# KNX-MultiExt_2.net
KiCad netlist of a schematic drawn in Altium Designer
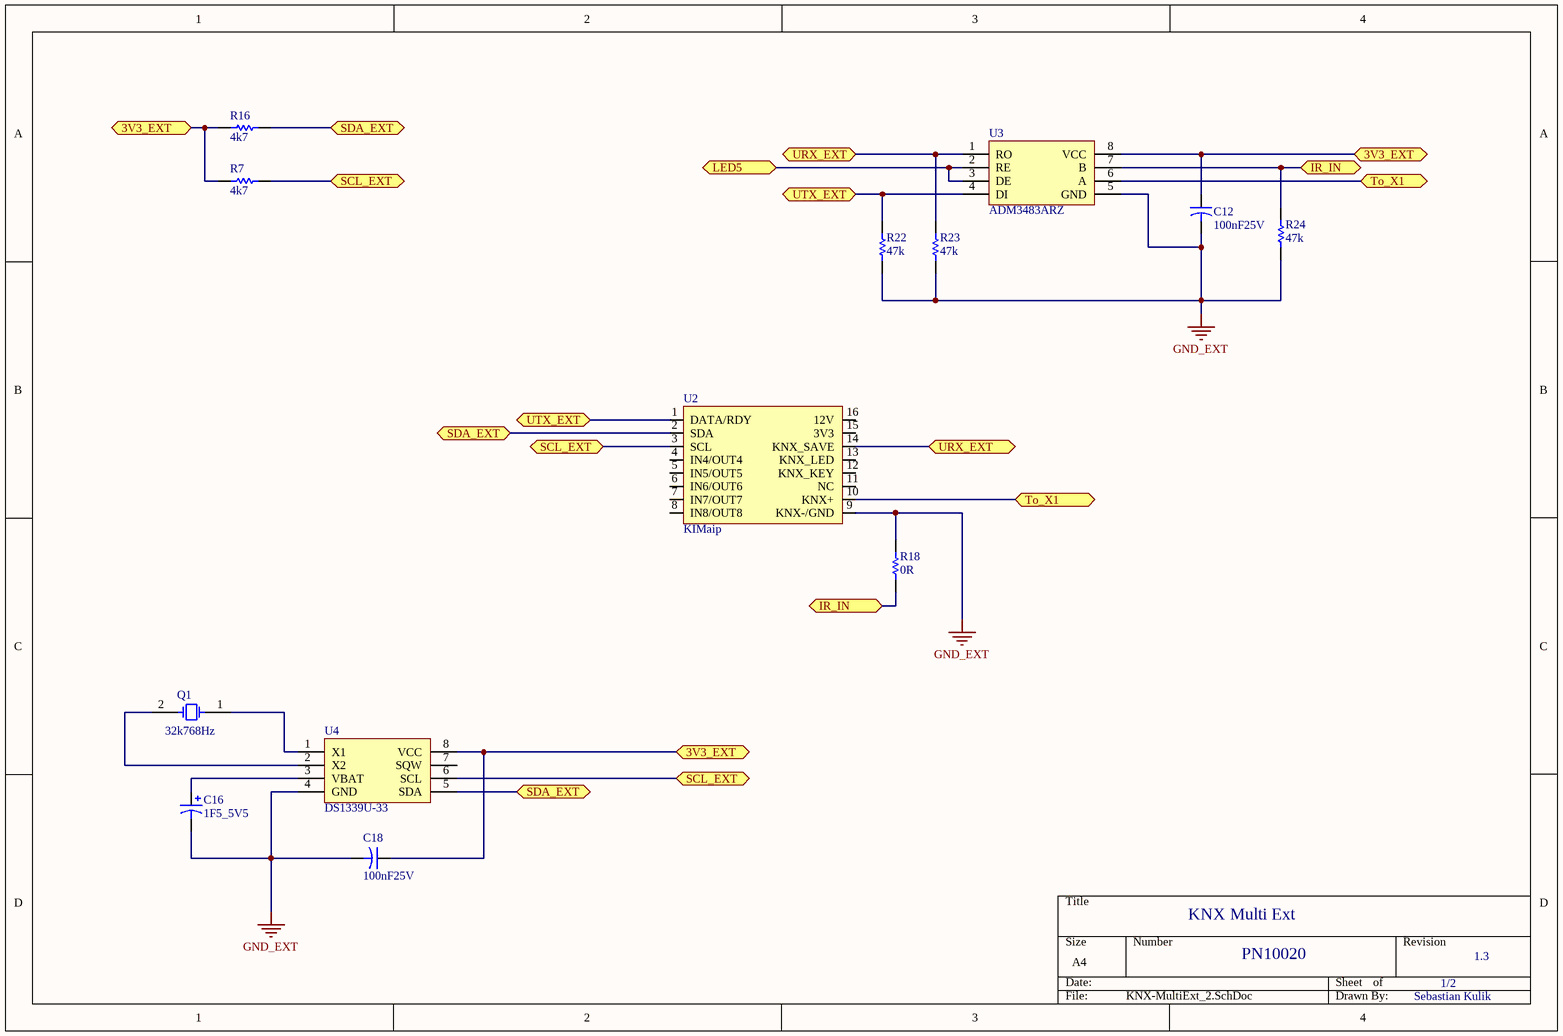
[diagram p0: KNX-MultiExt_2.SchDoc]

(export (version "E")
  (design (tool "Eeschema 10.0.6"))
  (components
    (comp (ref "C12")
      (value "100nF25V")
      (footprint "C0402")
      (description "AVX, X5R, 10%, 25V")
      (fields
        (field (name "MANUFACTURER") "AVX")
        (field (name "Comment") "100nF25V_0402")
        (field (name "PUBLISHER") "Sebastian Kulik")
      )
      (libsource (lib "Capacitors") (part "100nF25V_0402"))
    )
    (comp (ref "C16")
      (value "1F5_5V5")
      (footprint "Goldcap_B")
      (description "Panasonic, F series")
      (fields
        (field (name "MANUFACTURER") "Panasonic")
        (field (name "Comment") "1F5_5V5_POL")
        (field (name "PUBLISHER") "Sebastian Kulik")
      )
      (libsource (lib "Capacitors") (part "1F5_5V5_POL"))
    )
    (comp (ref "C18")
      (value "100nF25V")
      (footprint "C0402")
      (description "AVX, X5R, 10%, 25V")
      (fields
        (field (name "MANUFACTURER") "AVX")
        (field (name "Comment") "100nF25V_0402")
        (field (name "PUBLISHER") "Sebastian Kulik")
      )
      (libsource (lib "Capacitors") (part "100nF25V_0402"))
    )
    (comp (ref "Q1")
      (value "32k768Hz")
      (footprint "VT-200")
      (description "Crystal, 32.768kHz")
      (fields
        (field (name "MANUFACTURER") "Seiko")
        (field (name "Comment") "Crystal_32k768Hz")
        (field (name "PUBLISHER") "Sebastian Kulik")
      )
      (libsource (lib "Passives") (part "Crystal_32k768Hz"))
    )
    (comp (ref "R7")
      (value "4k7")
      (footprint "R0402")
      (description "Vishay CRCW series, 63mW, 1%")
      (fields
        (field (name "MANUFACTURER") "Vishay")
        (field (name "Comment") "4k7_0402")
        (field (name "PUBLISHER") "Sebastian Kulik")
      )
      (libsource (lib "Resistors") (part "4k7_0402"))
    )
    (comp (ref "R16")
      (value "4k7")
      (footprint "R0402")
      (description "Vishay CRCW series, 63mW, 1%")
      (fields
        (field (name "MANUFACTURER") "Vishay")
        (field (name "Comment") "4k7_0402")
        (field (name "PUBLISHER") "Sebastian Kulik")
      )
      (libsource (lib "Resistors") (part "4k7_0402"))
    )
    (comp (ref "R18")
      (value "0R")
      (footprint "R0603(1608)")
      (description "Vishay, CRCW series, 100mW")
      (fields
        (field (name "MANUFACTURER") "Vishay")
        (field (name "Comment") "0R_0603")
        (field (name "PUBLISHER") "Sebastian Kulik")
      )
      (libsource (lib "Resistors") (part "0R_0603"))
    )
    (comp (ref "R22")
      (value "47k")
      (footprint "R0402")
      (description "Vishay CRCW series, 63mW, 1%")
      (fields
        (field (name "MANUFACTURER") "Vishay")
        (field (name "Comment") "47k_0402")
        (field (name "PUBLISHER") "Sebastian Kulik")
      )
      (libsource (lib "Resistors") (part "47k_0402"))
    )
    (comp (ref "R23")
      (value "47k")
      (footprint "R0402")
      (description "Vishay CRCW series, 63mW, 1%")
      (fields
        (field (name "MANUFACTURER") "Vishay")
        (field (name "Comment") "47k_0402")
        (field (name "PUBLISHER") "Sebastian Kulik")
      )
      (libsource (lib "Resistors") (part "47k_0402"))
    )
    (comp (ref "R24")
      (value "47k")
      (footprint "R0402")
      (description "Vishay CRCW series, 63mW, 1%")
      (fields
        (field (name "MANUFACTURER") "Vishay")
        (field (name "Comment") "47k_0402")
        (field (name "PUBLISHER") "Sebastian Kulik")
      )
      (libsource (lib "Resistors") (part "47k_0402"))
    )
    (comp (ref "U2")
      (value "KIMaip")
      (footprint "KIMaip")
      (description "PoE, 12V")
      (fields (field (name "MANUFACTURER") "Tapko") (field (name "PUBLISHER") "Sebastian Kulik"))
      (libsource (lib "ICs") (part "KIMaip"))
    )
    (comp (ref "U3")
      (value "ADM3483ARZ")
      (footprint "SOIC8_N")
      (description "Transceiver, RS485/422")
      (fields (field (name "MANUFACTURER") "ADI") (field (name "PUBLISHER") "Sebastian Kulik"))
      (libsource (lib "ICs") (part "ADM3483ARZ"))
    )
    (comp (ref "U4")
      (value "DS1339U-33")
      (footprint "uSOP8")
      (description "RTC")
      (fields (field (name "MANUFACTURER") "Dallas") (field (name "PUBLISHER") "Sebastian Kulik"))
      (libsource (lib "ICs") (part "DS1339U-33"))
    )
  )
  (nets
    (net (code "1") (name "/3V3_EXT") (class "Default")
      (node (ref "C12") (pin "1") (pinfunction "1_1") (pintype "passive"))
      (node (ref "C18") (pin "1") (pinfunction "1_1") (pintype "passive"))
      (node (ref "R16") (pin "1") (pinfunction "1_1") (pintype "passive"))
      (node (ref "R7") (pin "1") (pinfunction "1_1") (pintype "passive"))
      (node (ref "U3") (pin "8") (pinfunction "VCC_8") (pintype "power_in"))
      (node (ref "U4") (pin "8") (pinfunction "VCC_8") (pintype "power_in"))
    )
    (net (code "2") (name "/IR_IN") (class "Default")
      (node (ref "R18") (pin "1") (pinfunction "1_1") (pintype "passive"))
      (node (ref "R24") (pin "2") (pinfunction "2_2") (pintype "passive"))
      (node (ref "U3") (pin "7") (pinfunction "B_7") (pintype "passive"))
    )
    (net (code "3") (name "/LED5") (class "Default")
      (node (ref "U3") (pin "2") (pinfunction "RE_2") (pintype "passive"))
      (node (ref "U3") (pin "3") (pinfunction "DE_3") (pintype "passive"))
    )
    (net (code "4") (name "/SCL_EXT") (class "Default")
      (node (ref "R7") (pin "2") (pinfunction "2_2") (pintype "passive"))
      (node (ref "U2") (pin "3") (pinfunction "SCL_3") (pintype "passive"))
      (node (ref "U4") (pin "6") (pinfunction "SCL_6") (pintype "passive"))
    )
    (net (code "5") (name "/SDA_EXT") (class "Default")
      (node (ref "R16") (pin "2") (pinfunction "2_2") (pintype "passive"))
      (node (ref "U2") (pin "2") (pinfunction "SDA_2") (pintype "passive"))
      (node (ref "U4") (pin "5") (pinfunction "SDA_5") (pintype "passive"))
    )
    (net (code "6") (name "/To_X1") (class "Default")
      (node (ref "U2") (pin "10") (pinfunction "KNX+_10") (pintype "passive"))
      (node (ref "U3") (pin "6") (pinfunction "A_6") (pintype "passive"))
    )
    (net (code "7") (name "/URX_EXT") (class "Default")
      (node (ref "R23") (pin "2") (pinfunction "2_2") (pintype "passive"))
      (node (ref "U2") (pin "14") (pinfunction "KNX_SAVE_14") (pintype "passive"))
      (node (ref "U3") (pin "1") (pinfunction "RO_1") (pintype "passive"))
    )
    (net (code "8") (name "/UTX_EXT") (class "Default")
      (node (ref "R22") (pin "2") (pinfunction "2_2") (pintype "passive"))
      (node (ref "U2") (pin "1") (pinfunction "DATA/RDY_1") (pintype "passive"))
      (node (ref "U3") (pin "4") (pinfunction "DI_4") (pintype "passive"))
    )
    (net (code "9") (name "GND_EXT") (class "Default")
      (node (ref "C12") (pin "2") (pinfunction "2_2") (pintype "passive"))
      (node (ref "C16") (pin "2") (pinfunction "2_2") (pintype "passive"))
      (node (ref "C18") (pin "2") (pinfunction "2_2") (pintype "passive"))
      (node (ref "R18") (pin "2") (pinfunction "2_2") (pintype "passive"))
      (node (ref "R22") (pin "1") (pinfunction "1_1") (pintype "passive"))
      (node (ref "R23") (pin "1") (pinfunction "1_1") (pintype "passive"))
      (node (ref "R24") (pin "1") (pinfunction "1_1") (pintype "passive"))
      (node (ref "U2") (pin "9") (pinfunction "KNX-/GND_9") (pintype "passive"))
      (node (ref "U3") (pin "5") (pinfunction "GND_5") (pintype "passive"))
      (node (ref "U4") (pin "4") (pinfunction "GND_4") (pintype "passive"))
    )
    (net (code "10") (name "Net-(Q1-E{slash}D)") (class "Default")
      (node (ref "Q1") (pin "1") (pinfunction "E/D_1") (pintype "passive"))
      (node (ref "U4") (pin "1") (pinfunction "X1_1") (pintype "passive"))
    )
    (net (code "11") (name "Net-(Q1-GND)") (class "Default")
      (node (ref "Q1") (pin "2") (pinfunction "GND_2") (pintype "passive"))
      (node (ref "U4") (pin "2") (pinfunction "X2_2") (pintype "passive"))
    )
    (net (code "12") (name "Net-(U4-VBAT)") (class "Default")
      (node (ref "C16") (pin "1") (pinfunction "1_1") (pintype "passive"))
      (node (ref "U4") (pin "3") (pinfunction "VBAT_3") (pintype "passive"))
    )
    (net (code "13") (name "unconnected-(U2-3V3-Pad15)") (class "Default")
      (node (ref "U2") (pin "15") (pinfunction "3V3_15") (pintype "passive"))
    )
    (net (code "14") (name "unconnected-(U2-12V-Pad16)") (class "Default")
      (node (ref "U2") (pin "16") (pinfunction "12V_16") (pintype "passive"))
    )
    (net (code "15") (name "unconnected-(U2-IN4{slash}OUT4-Pad4)") (class "Default")
      (node (ref "U2") (pin "4") (pinfunction "IN4/OUT4_4") (pintype "passive"))
    )
    (net (code "16") (name "unconnected-(U2-IN5{slash}OUT5-Pad5)") (class "Default")
      (node (ref "U2") (pin "5") (pinfunction "IN5/OUT5_5") (pintype "passive"))
    )
    (net (code "17") (name "unconnected-(U2-IN6{slash}OUT6-Pad6)") (class "Default")
      (node (ref "U2") (pin "6") (pinfunction "IN6/OUT6_6") (pintype "passive"))
    )
    (net (code "18") (name "unconnected-(U2-IN7{slash}OUT7-Pad7)") (class "Default")
      (node (ref "U2") (pin "7") (pinfunction "IN7/OUT7_7") (pintype "passive"))
    )
    (net (code "19") (name "unconnected-(U2-IN8{slash}OUT8-Pad8)") (class "Default")
      (node (ref "U2") (pin "8") (pinfunction "IN8/OUT8_8") (pintype "power_in"))
    )
    (net (code "20") (name "unconnected-(U2-KNX_KEY-Pad12)") (class "Default")
      (node (ref "U2") (pin "12") (pinfunction "KNX_KEY_12") (pintype "passive"))
    )
    (net (code "21") (name "unconnected-(U2-KNX_LED-Pad13)") (class "Default")
      (node (ref "U2") (pin "13") (pinfunction "KNX_LED_13") (pintype "passive"))
    )
    (net (code "22") (name "unconnected-(U2-NC-Pad11)") (class "Default")
      (node (ref "U2") (pin "11") (pinfunction "NC_11") (pintype "passive"))
    )
    (net (code "23") (name "unconnected-(U4-SQW-Pad7)") (class "Default")
      (node (ref "U4") (pin "7") (pinfunction "SQW_7") (pintype "passive"))
    )
  )
)
